# Sensoray_Breakout_26.net
KiCad netlist of a schematic drawn in EAGLE
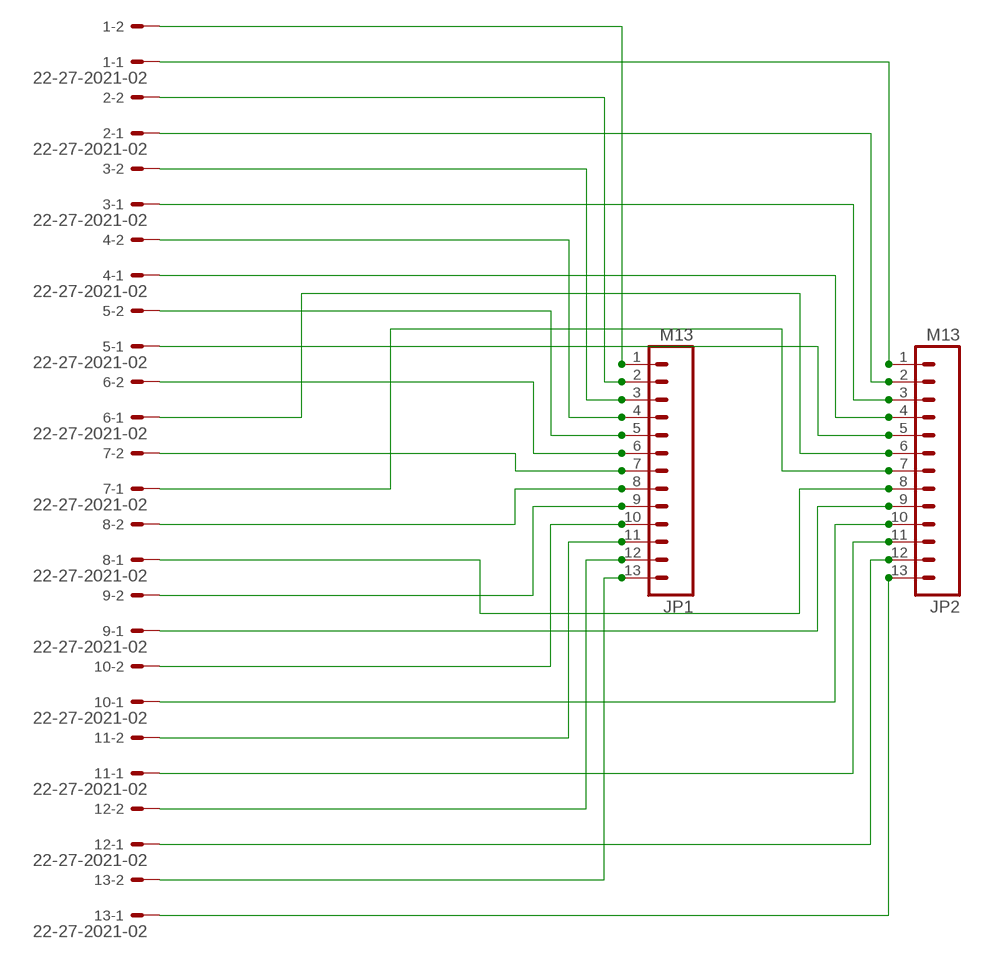
[diagram p0: schematic, sheet 1]

(export (version "E")
  (design (tool "Eeschema 10.0.6"))
  (components
    (comp (ref "1")
      (value "22-27-2021-02")
      (footprint "eagle-import:6410-02")
      (libsource (lib "eagle-import") (part "22-?-0227-2021"))
    )
    (comp (ref "2")
      (value "22-27-2021-02")
      (footprint "eagle-import:6410-02")
      (libsource (lib "eagle-import") (part "22-?-0227-2021"))
    )
    (comp (ref "3")
      (value "22-27-2021-02")
      (footprint "eagle-import:6410-02")
      (libsource (lib "eagle-import") (part "22-?-0227-2021"))
    )
    (comp (ref "4")
      (value "22-27-2021-02")
      (footprint "eagle-import:6410-02")
      (libsource (lib "eagle-import") (part "22-?-0227-2021"))
    )
    (comp (ref "5")
      (value "22-27-2021-02")
      (footprint "eagle-import:6410-02")
      (libsource (lib "eagle-import") (part "22-?-0227-2021"))
    )
    (comp (ref "6")
      (value "22-27-2021-02")
      (footprint "eagle-import:6410-02")
      (libsource (lib "eagle-import") (part "22-?-0227-2021"))
    )
    (comp (ref "7")
      (value "22-27-2021-02")
      (footprint "eagle-import:6410-02")
      (libsource (lib "eagle-import") (part "22-?-0227-2021"))
    )
    (comp (ref "8")
      (value "22-27-2021-02")
      (footprint "eagle-import:6410-02")
      (libsource (lib "eagle-import") (part "22-?-0227-2021"))
    )
    (comp (ref "9")
      (value "22-27-2021-02")
      (footprint "eagle-import:6410-02")
      (libsource (lib "eagle-import") (part "22-?-0227-2021"))
    )
    (comp (ref "10")
      (value "22-27-2021-02")
      (footprint "eagle-import:6410-02")
      (libsource (lib "eagle-import") (part "22-?-0227-2021"))
    )
    (comp (ref "11")
      (value "22-27-2021-02")
      (footprint "eagle-import:6410-02")
      (libsource (lib "eagle-import") (part "22-?-0227-2021"))
    )
    (comp (ref "12")
      (value "22-27-2021-02")
      (footprint "eagle-import:6410-02")
      (libsource (lib "eagle-import") (part "22-?-0227-2021"))
    )
    (comp (ref "13")
      (value "22-27-2021-02")
      (footprint "eagle-import:6410-02")
      (libsource (lib "eagle-import") (part "22-?-0227-2021"))
    )
    (comp (ref "JP1")
      (value "M13")
      (footprint "eagle-import:1X13")
      (libsource (lib "eagle-import") (part "M13"))
    )
    (comp (ref "JP2")
      (value "M13")
      (footprint "eagle-import:1X13")
      (libsource (lib "eagle-import") (part "M13"))
    )
  )
  (nets
    (net (code "1") (name "Net-(1A-S)") (class "Default")
      (node (ref "1") (pin "1") (pinfunction "S_1") (pintype "passive"))
      (node (ref "JP2") (pin "1") (pinfunction "1_1") (pintype "passive"))
    )
    (net (code "2") (name "Net-(1B-S)") (class "Default")
      (node (ref "1") (pin "2") (pinfunction "S_2") (pintype "passive"))
      (node (ref "JP1") (pin "1") (pinfunction "1_1") (pintype "passive"))
    )
    (net (code "3") (name "Net-(2A-S)") (class "Default")
      (node (ref "2") (pin "1") (pinfunction "S_1") (pintype "passive"))
      (node (ref "JP2") (pin "2") (pinfunction "2_2") (pintype "passive"))
    )
    (net (code "4") (name "Net-(2B-S)") (class "Default")
      (node (ref "2") (pin "2") (pinfunction "S_2") (pintype "passive"))
      (node (ref "JP1") (pin "2") (pinfunction "2_2") (pintype "passive"))
    )
    (net (code "5") (name "Net-(3A-S)") (class "Default")
      (node (ref "3") (pin "1") (pinfunction "S_1") (pintype "passive"))
      (node (ref "JP2") (pin "3") (pinfunction "3_3") (pintype "passive"))
    )
    (net (code "6") (name "Net-(3B-S)") (class "Default")
      (node (ref "3") (pin "2") (pinfunction "S_2") (pintype "passive"))
      (node (ref "JP1") (pin "3") (pinfunction "3_3") (pintype "passive"))
    )
    (net (code "7") (name "Net-(4A-S)") (class "Default")
      (node (ref "4") (pin "1") (pinfunction "S_1") (pintype "passive"))
      (node (ref "JP2") (pin "4") (pinfunction "4_4") (pintype "passive"))
    )
    (net (code "8") (name "Net-(4B-S)") (class "Default")
      (node (ref "4") (pin "2") (pinfunction "S_2") (pintype "passive"))
      (node (ref "JP1") (pin "4") (pinfunction "4_4") (pintype "passive"))
    )
    (net (code "9") (name "Net-(5A-S)") (class "Default")
      (node (ref "5") (pin "1") (pinfunction "S_1") (pintype "passive"))
      (node (ref "JP2") (pin "5") (pinfunction "5_5") (pintype "passive"))
    )
    (net (code "10") (name "Net-(5B-S)") (class "Default")
      (node (ref "5") (pin "2") (pinfunction "S_2") (pintype "passive"))
      (node (ref "JP1") (pin "5") (pinfunction "5_5") (pintype "passive"))
    )
    (net (code "11") (name "Net-(6A-S)") (class "Default")
      (node (ref "6") (pin "1") (pinfunction "S_1") (pintype "passive"))
      (node (ref "JP2") (pin "6") (pinfunction "6_6") (pintype "passive"))
    )
    (net (code "12") (name "Net-(6B-S)") (class "Default")
      (node (ref "6") (pin "2") (pinfunction "S_2") (pintype "passive"))
      (node (ref "JP1") (pin "6") (pinfunction "6_6") (pintype "passive"))
    )
    (net (code "13") (name "Net-(7A-S)") (class "Default")
      (node (ref "7") (pin "1") (pinfunction "S_1") (pintype "passive"))
      (node (ref "JP2") (pin "7") (pinfunction "7_7") (pintype "passive"))
    )
    (net (code "14") (name "Net-(7B-S)") (class "Default")
      (node (ref "7") (pin "2") (pinfunction "S_2") (pintype "passive"))
      (node (ref "JP1") (pin "7") (pinfunction "7_7") (pintype "passive"))
    )
    (net (code "15") (name "Net-(8A-S)") (class "Default")
      (node (ref "8") (pin "1") (pinfunction "S_1") (pintype "passive"))
      (node (ref "JP2") (pin "8") (pinfunction "8_8") (pintype "passive"))
    )
    (net (code "16") (name "Net-(8B-S)") (class "Default")
      (node (ref "8") (pin "2") (pinfunction "S_2") (pintype "passive"))
      (node (ref "JP1") (pin "8") (pinfunction "8_8") (pintype "passive"))
    )
    (net (code "17") (name "Net-(9A-S)") (class "Default")
      (node (ref "9") (pin "1") (pinfunction "S_1") (pintype "passive"))
      (node (ref "JP2") (pin "9") (pinfunction "9_9") (pintype "passive"))
    )
    (net (code "18") (name "Net-(9B-S)") (class "Default")
      (node (ref "9") (pin "2") (pinfunction "S_2") (pintype "passive"))
      (node (ref "JP1") (pin "9") (pinfunction "9_9") (pintype "passive"))
    )
    (net (code "19") (name "Net-(10A-S)") (class "Default")
      (node (ref "10") (pin "1") (pinfunction "S_1") (pintype "passive"))
      (node (ref "JP2") (pin "10") (pinfunction "10_10") (pintype "passive"))
    )
    (net (code "20") (name "Net-(10B-S)") (class "Default")
      (node (ref "10") (pin "2") (pinfunction "S_2") (pintype "passive"))
      (node (ref "JP1") (pin "10") (pinfunction "10_10") (pintype "passive"))
    )
    (net (code "21") (name "Net-(11A-S)") (class "Default")
      (node (ref "11") (pin "1") (pinfunction "S_1") (pintype "passive"))
      (node (ref "JP2") (pin "11") (pinfunction "11_11") (pintype "passive"))
    )
    (net (code "22") (name "Net-(11B-S)") (class "Default")
      (node (ref "11") (pin "2") (pinfunction "S_2") (pintype "passive"))
      (node (ref "JP1") (pin "11") (pinfunction "11_11") (pintype "passive"))
    )
    (net (code "23") (name "Net-(12A-S)") (class "Default")
      (node (ref "12") (pin "1") (pinfunction "S_1") (pintype "passive"))
      (node (ref "JP2") (pin "12") (pinfunction "12_12") (pintype "passive"))
    )
    (net (code "24") (name "Net-(12B-S)") (class "Default")
      (node (ref "12") (pin "2") (pinfunction "S_2") (pintype "passive"))
      (node (ref "JP1") (pin "12") (pinfunction "12_12") (pintype "passive"))
    )
    (net (code "25") (name "Net-(13A-S)") (class "Default")
      (node (ref "13") (pin "1") (pinfunction "S_1") (pintype "passive"))
      (node (ref "JP2") (pin "13") (pinfunction "13_13") (pintype "passive"))
    )
    (net (code "26") (name "Net-(13B-S)") (class "Default")
      (node (ref "13") (pin "2") (pinfunction "S_2") (pintype "passive"))
      (node (ref "JP1") (pin "13") (pinfunction "13_13") (pintype "passive"))
    )
  )
)
